# Comparator.net
KiCad netlist of a schematic drawn in Altium Designer
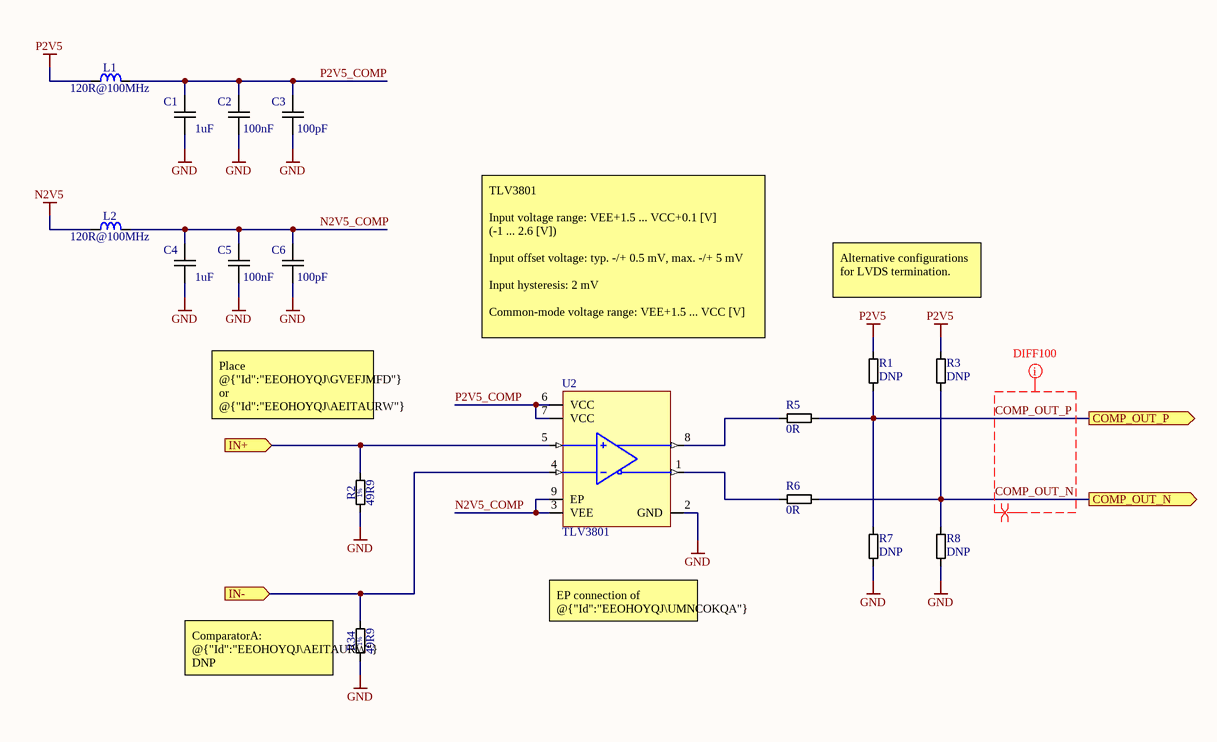
[diagram p0: Comparator.SchDoc]

(export (version "E")
  (design (tool "Eeschema 10.0.6"))
  (components
    (comp (ref "C1")
      (value "1uF")
      (footprint "CAPC0603X90N")
      (description "Non-polarised capacitor")
      (fields (field (name "MANUFACTURER PART NUMBER") "CL10B105KO8NNNC"))
      (libsource (lib "Capacitors") (part "Capacitor - non polarized"))
    )
    (comp (ref "C2")
      (value "100nF")
      (footprint "CAPC0603X90N")
      (description "Non-polarised capacitor")
      (fields (field (name "MANUFACTURER PART NUMBER") "VJ0603Y104KXJCW1BC"))
      (libsource (lib "Capacitors") (part "Capacitor - non polarized"))
    )
    (comp (ref "C3")
      (value "100pF")
      (footprint "CAPC0603X90N")
      (description "Non-polarised capacitor")
      (fields (field (name "MANUFACTURER PART NUMBER") "06035C101JAT2A"))
      (libsource (lib "Capacitors") (part "Capacitor - non polarized"))
    )
    (comp (ref "C4")
      (value "1uF")
      (footprint "CAPC0603X90N")
      (description "Non-polarised capacitor")
      (fields (field (name "MANUFACTURER PART NUMBER") "CL10B105KO8NNNC"))
      (libsource (lib "Capacitors") (part "Capacitor - non polarized"))
    )
    (comp (ref "C5")
      (value "100nF")
      (footprint "CAPC0603X90N")
      (description "Non-polarised capacitor")
      (fields (field (name "MANUFACTURER PART NUMBER") "VJ0603Y104KXJCW1BC"))
      (libsource (lib "Capacitors") (part "Capacitor - non polarized"))
    )
    (comp (ref "C6")
      (value "100pF")
      (footprint "CAPC0603X90N")
      (description "Non-polarised capacitor")
      (fields (field (name "MANUFACTURER PART NUMBER") "06035C101JAT2A"))
      (libsource (lib "Capacitors") (part "Capacitor - non polarized"))
    )
    (comp (ref "L1")
      (value "120R@100MHz")
      (footprint "INDC0603X90N")
      (description "Ferrite Bead")
      (fields (field (name "MANUFACTURER PART NUMBER") "BLM18PG121SN1D") (field (name "TOLERANCE") "25%"))
      (libsource (lib "Inductors") (part "Inductor"))
    )
    (comp (ref "L2")
      (value "120R@100MHz")
      (footprint "INDC0603X90N")
      (description "Ferrite Bead")
      (fields (field (name "MANUFACTURER PART NUMBER") "BLM18PG121SN1D") (field (name "TOLERANCE") "25%"))
      (libsource (lib "Inductors") (part "Inductor"))
    )
    (comp (ref "R1")
      (value "DNP")
      (footprint "RESC0402X40N")
      (description "General Purpose Thick Film Chip Resistor")
      (fields (field (name "VOLTAGE") "50V"))
      (libsource (lib "Resistors") (part "Resistor - Generic"))
    )
    (comp (ref "R2")
      (value "49R9")
      (footprint "RESC0402X40N")
      (description "General Purpose Thick Film Chip Resistor")
      (fields (field (name "MANUFACTURER PART NUMBER") "RC0402FR-0749R9L") (field (name "TOLERANCE") "1%"))
      (libsource (lib "Resistors") (part "Resistor - 1%"))
    )
    (comp (ref "R3")
      (value "DNP")
      (footprint "RESC0402X40N")
      (description "General Purpose Thick Film Chip Resistor")
      (fields (field (name "VOLTAGE") "50V"))
      (libsource (lib "Resistors") (part "Resistor - Generic"))
    )
    (comp (ref "R5")
      (value "0R")
      (footprint "RESC0402X40N")
      (description "General Purpose Thick Film Chip Resistor")
      (fields
        (field (name "MANUFACTURER PART NUMBER") "CRCW04020000Z0EDC")
        (field (name "TOLERANCE") "20mOhm")
      )
      (libsource (lib "Resistors") (part "Resistor - Generic"))
    )
    (comp (ref "R6")
      (value "0R")
      (footprint "RESC0402X40N")
      (description "General Purpose Thick Film Chip Resistor")
      (fields
        (field (name "MANUFACTURER PART NUMBER") "CRCW04020000Z0EDC")
        (field (name "TOLERANCE") "20mOhm")
      )
      (libsource (lib "Resistors") (part "Resistor - Generic"))
    )
    (comp (ref "R7")
      (value "DNP")
      (footprint "RESC0402X40N")
      (description "General Purpose Thick Film Chip Resistor")
      (fields (field (name "VOLTAGE") "50V"))
      (libsource (lib "Resistors") (part "Resistor - Generic"))
    )
    (comp (ref "R8")
      (value "DNP")
      (footprint "RESC0402X40N")
      (description "General Purpose Thick Film Chip Resistor")
      (fields (field (name "VOLTAGE") "50V"))
      (libsource (lib "Resistors") (part "Resistor - Generic"))
    )
    (comp (ref "R34")
      (value "49R9")
      (footprint "RESC0402X40N")
      (description "General Purpose Thick Film Chip Resistor")
      (fields (field (name "MANUFACTURER PART NUMBER") "RC0402FR-0749R9L") (field (name "TOLERANCE") "1%"))
      (libsource (lib "Resistors") (part "Resistor - 1%"))
    )
    (comp (ref "U2")
      (value "TLV3801")
      (footprint "WSON50P200X200X80-9N")
      (description "225-ps High-Speed Comparator with LVDS Outputs")
      (fields (field (name "MANUFACTURER PART NUMBER") "TLV3801DSG(_)"))
      (libsource (lib "ICs_and_Semiconductors") (part "TLV3801"))
    )
  )
  (nets
    (net (code "1") (name "/COMP_OUT_N") (class "Default")
      (node (ref "R3") (pin "1") (pinfunction "1_1") (pintype "passive"))
      (node (ref "R6") (pin "2") (pinfunction "2_2") (pintype "passive"))
      (node (ref "R8") (pin "2") (pinfunction "2_2") (pintype "passive"))
    )
    (net (code "2") (name "/COMP_OUT_P") (class "Default")
      (node (ref "R1") (pin "1") (pinfunction "1_1") (pintype "passive"))
      (node (ref "R5") (pin "2") (pinfunction "2_2") (pintype "passive"))
      (node (ref "R7") (pin "2") (pinfunction "2_2") (pintype "passive"))
    )
    (net (code "3") (name "/IN+") (class "Default")
      (node (ref "R2") (pin "2") (pinfunction "2_2") (pintype "passive"))
      (node (ref "U2") (pin "5") (pinfunction "IN+_5") (pintype "input"))
    )
    (net (code "4") (name "/IN-") (class "Default")
      (node (ref "R34") (pin "2") (pinfunction "2_2") (pintype "passive"))
      (node (ref "U2") (pin "4") (pinfunction "IN-_4") (pintype "input"))
    )
    (net (code "5") (name "/N2V5_COMP") (class "Default")
      (node (ref "C4") (pin "1") (pinfunction "1_1") (pintype "passive"))
      (node (ref "C5") (pin "1") (pinfunction "1_1") (pintype "passive"))
      (node (ref "C6") (pin "1") (pinfunction "1_1") (pintype "passive"))
      (node (ref "L2") (pin "2") (pinfunction "2_2") (pintype "passive"))
      (node (ref "U2") (pin "3") (pinfunction "VEE_3") (pintype "power_in"))
      (node (ref "U2") (pin "9") (pinfunction "EP_9") (pintype "power_in"))
    )
    (net (code "6") (name "/P2V5_COMP") (class "Default")
      (node (ref "C1") (pin "1") (pinfunction "1_1") (pintype "passive"))
      (node (ref "C2") (pin "1") (pinfunction "1_1") (pintype "passive"))
      (node (ref "C3") (pin "1") (pinfunction "1_1") (pintype "passive"))
      (node (ref "L1") (pin "2") (pinfunction "2_2") (pintype "passive"))
      (node (ref "U2") (pin "6") (pinfunction "VCC_6") (pintype "power_in"))
      (node (ref "U2") (pin "7") (pinfunction "VCC_7") (pintype "power_in"))
    )
    (net (code "7") (name "GND") (class "Default")
      (node (ref "C1") (pin "2") (pinfunction "2_2") (pintype "passive"))
      (node (ref "C2") (pin "2") (pinfunction "2_2") (pintype "passive"))
      (node (ref "C3") (pin "2") (pinfunction "2_2") (pintype "passive"))
      (node (ref "C4") (pin "2") (pinfunction "2_2") (pintype "passive"))
      (node (ref "C5") (pin "2") (pinfunction "2_2") (pintype "passive"))
      (node (ref "C6") (pin "2") (pinfunction "2_2") (pintype "passive"))
      (node (ref "R2") (pin "1") (pinfunction "1_1") (pintype "passive"))
      (node (ref "R34") (pin "1") (pinfunction "1_1") (pintype "passive"))
      (node (ref "R7") (pin "1") (pinfunction "1_1") (pintype "passive"))
      (node (ref "R8") (pin "1") (pinfunction "1_1") (pintype "passive"))
      (node (ref "U2") (pin "2") (pinfunction "GND_2") (pintype "power_in"))
    )
    (net (code "8") (name "N2V5") (class "Default")
      (node (ref "L2") (pin "1") (pinfunction "1_1") (pintype "passive"))
    )
    (net (code "9") (name "Net-(U2-OUT+)") (class "Default")
      (node (ref "R5") (pin "1") (pinfunction "1_1") (pintype "passive"))
      (node (ref "U2") (pin "8") (pinfunction "OUT+_8") (pintype "output"))
    )
    (net (code "10") (name "Net-(U2-OUT-)") (class "Default")
      (node (ref "R6") (pin "1") (pinfunction "1_1") (pintype "passive"))
      (node (ref "U2") (pin "1") (pinfunction "OUT-_1") (pintype "output"))
    )
    (net (code "11") (name "P2V5") (class "Default")
      (node (ref "L1") (pin "1") (pinfunction "1_1") (pintype "passive"))
      (node (ref "R1") (pin "2") (pinfunction "2_2") (pintype "passive"))
      (node (ref "R3") (pin "2") (pinfunction "2_2") (pintype "passive"))
    )
  )
)
